# 130808_AriloRX_FINAL_LOGO.net
KiCad netlist of a schematic drawn in EAGLE
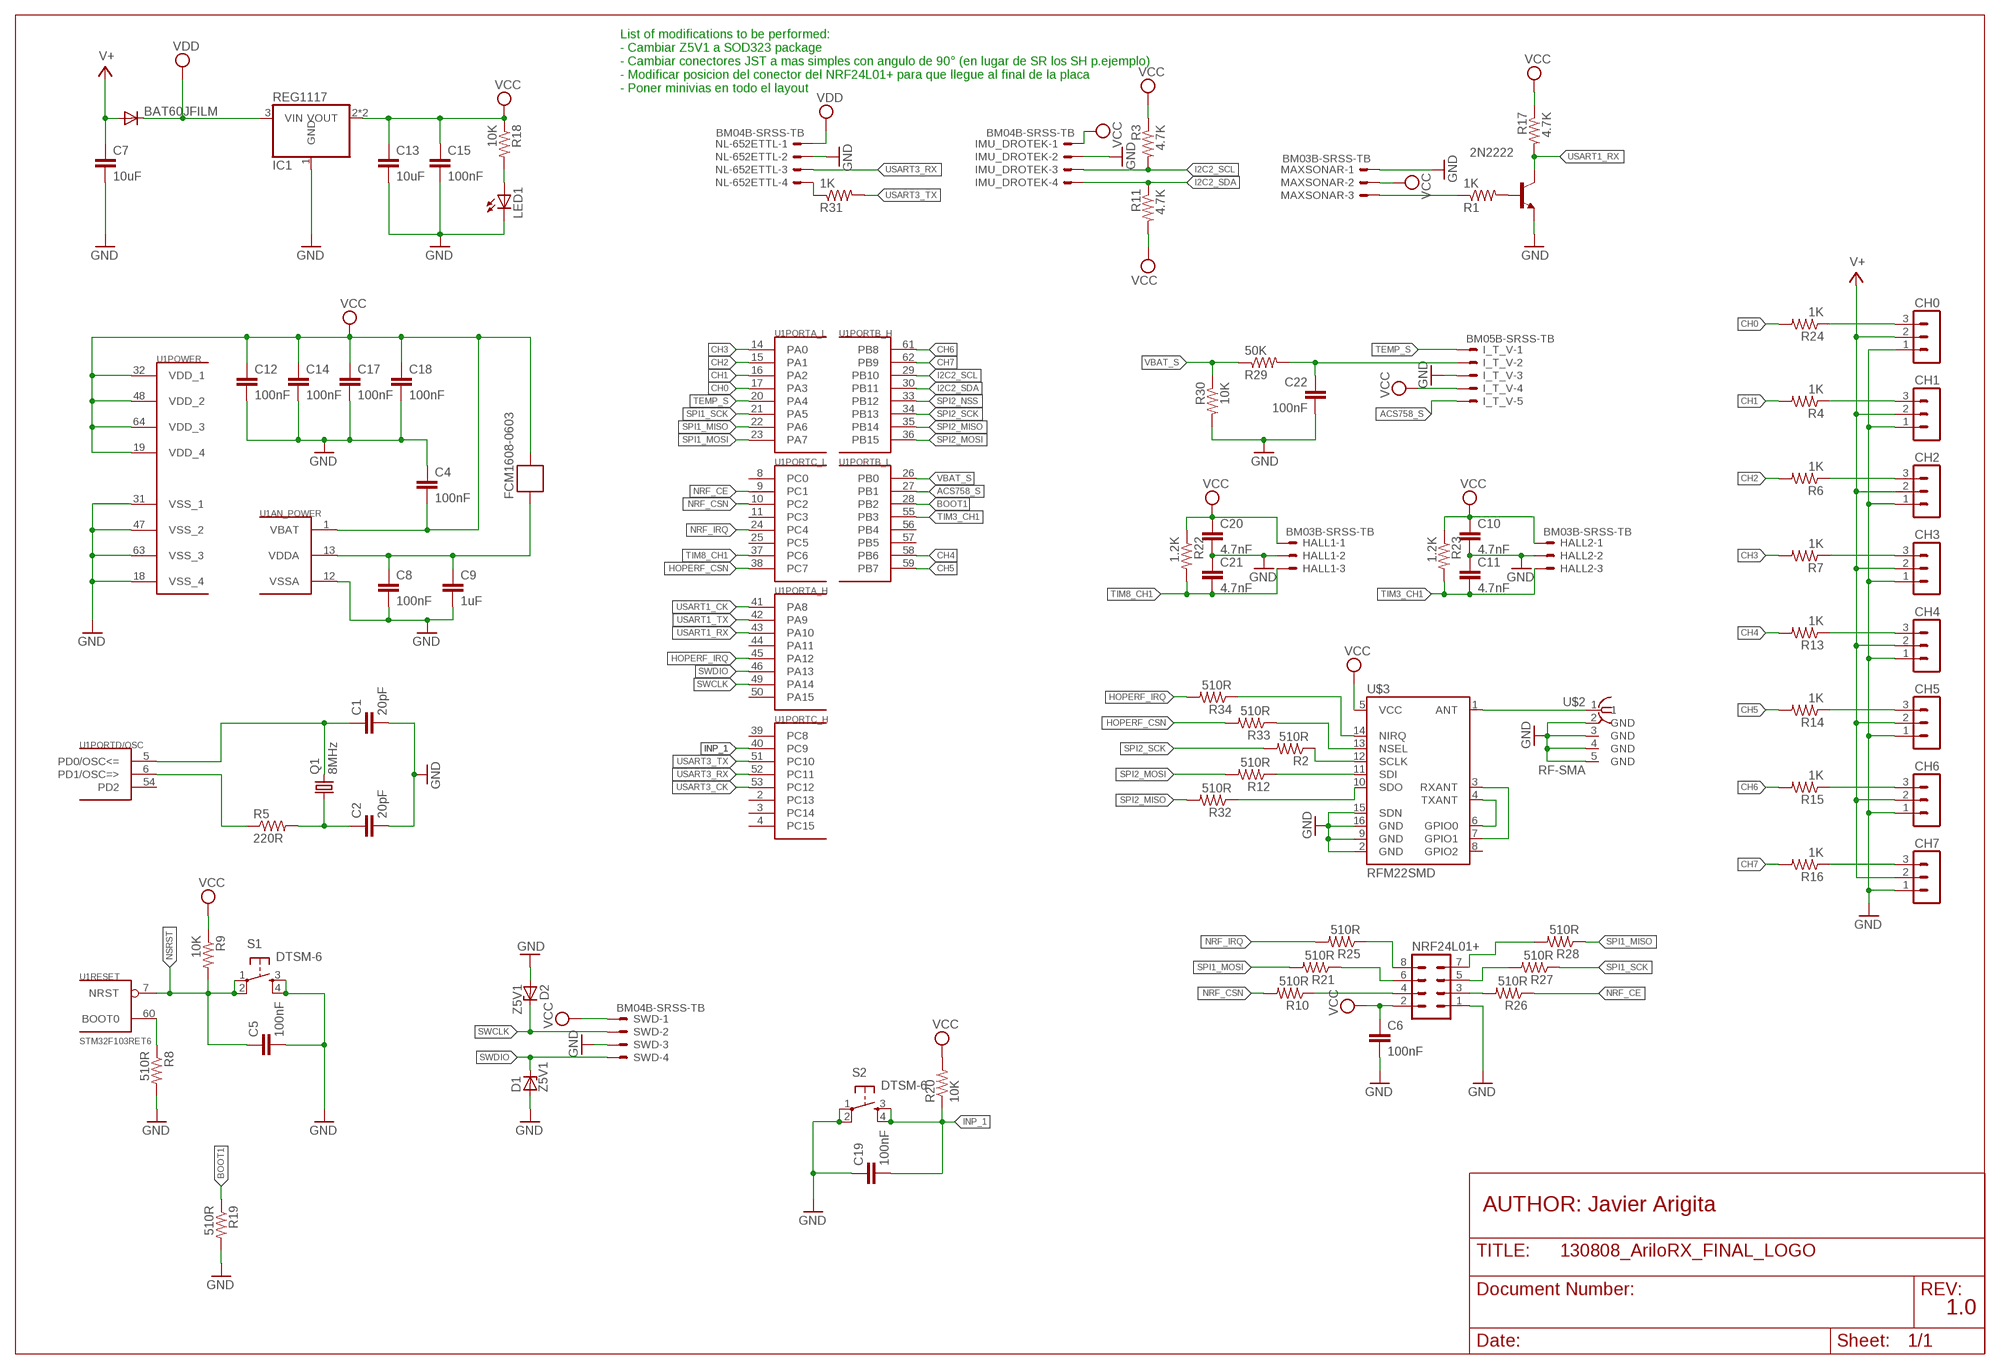
[diagram p0: schematic, sheet 1]

(export (version "E")
  (design (tool "Eeschema 10.0.6"))
  (components
    (comp (ref "2N2222")
      (value "MMBT2222ALT1-NPN-SOT23-BEC")
      (footprint "eagle-import:SOT23-BEC")
      (libsource (lib "eagle-import") (part "-NPN-SOT23-BECMMBT2222ALT1"))
    )
    (comp (ref "BAT60JFILM")
      (value "DIODE-SOD323-R")
      (footprint "eagle-import:SOD323-R")
      (libsource (lib "eagle-import") (part "DIODE-SOD323-R"))
    )
    (comp (ref "C1")
      (value "20pF")
      (footprint "eagle-import:C0805")
      (libsource (lib "eagle-import") (part "C-EUC0805"))
    )
    (comp (ref "C2")
      (value "20pF")
      (footprint "eagle-import:C0805")
      (libsource (lib "eagle-import") (part "C-EUC0805"))
    )
    (comp (ref "C4")
      (value "100nF")
      (footprint "eagle-import:C0805")
      (libsource (lib "eagle-import") (part "C-EUC0805"))
    )
    (comp (ref "C5")
      (value "100nF")
      (footprint "eagle-import:C0805")
      (libsource (lib "eagle-import") (part "C-EUC0805"))
    )
    (comp (ref "C6")
      (value "100nF")
      (footprint "eagle-import:C0805")
      (libsource (lib "eagle-import") (part "C-EUC0805"))
    )
    (comp (ref "C7")
      (value "10uF")
      (footprint "eagle-import:C3216")
      (libsource (lib "eagle-import") (part "resistor_C-EUC3216"))
    )
    (comp (ref "C8")
      (value "100nF")
      (footprint "eagle-import:C0805")
      (libsource (lib "eagle-import") (part "C-EUC0805"))
    )
    (comp (ref "C9")
      (value "1uF")
      (footprint "eagle-import:C3216")
      (libsource (lib "eagle-import") (part "resistor_C-EUC3216"))
    )
    (comp (ref "C10")
      (value "4.7nF")
      (footprint "eagle-import:C0805")
      (libsource (lib "eagle-import") (part "C-EUC0805"))
    )
    (comp (ref "C11")
      (value "4.7nF")
      (footprint "eagle-import:C0805")
      (libsource (lib "eagle-import") (part "C-EUC0805"))
    )
    (comp (ref "C12")
      (value "100nF")
      (footprint "eagle-import:C0805")
      (libsource (lib "eagle-import") (part "C-EUC0805"))
    )
    (comp (ref "C13")
      (value "10uF")
      (footprint "eagle-import:C3216")
      (libsource (lib "eagle-import") (part "resistor_C-EUC3216"))
    )
    (comp (ref "C14")
      (value "100nF")
      (footprint "eagle-import:C0805")
      (libsource (lib "eagle-import") (part "C-EUC0805"))
    )
    (comp (ref "C15")
      (value "100nF")
      (footprint "eagle-import:C0805")
      (libsource (lib "eagle-import") (part "C-EUC0805"))
    )
    (comp (ref "C17")
      (value "100nF")
      (footprint "eagle-import:C0805")
      (libsource (lib "eagle-import") (part "C-EUC0805"))
    )
    (comp (ref "C18")
      (value "100nF")
      (footprint "eagle-import:C0805")
      (libsource (lib "eagle-import") (part "C-EUC0805"))
    )
    (comp (ref "C19")
      (value "100nF")
      (footprint "eagle-import:C0805")
      (libsource (lib "eagle-import") (part "C-EUC0805"))
    )
    (comp (ref "C20")
      (value "4.7nF")
      (footprint "eagle-import:C0805")
      (libsource (lib "eagle-import") (part "C-EUC0805"))
    )
    (comp (ref "C21")
      (value "4.7nF")
      (footprint "eagle-import:C0805")
      (libsource (lib "eagle-import") (part "C-EUC0805"))
    )
    (comp (ref "C22")
      (value "100nF")
      (footprint "eagle-import:C0805")
      (libsource (lib "eagle-import") (part "C-EUC0805"))
    )
    (comp (ref "CH0")
      (value "MA03-1")
      (footprint "eagle-import:MA03-1")
      (libsource (lib "eagle-import") (part "MA03-1"))
    )
    (comp (ref "CH1")
      (value "MA03-1")
      (footprint "eagle-import:MA03-1")
      (libsource (lib "eagle-import") (part "MA03-1"))
    )
    (comp (ref "CH2")
      (value "MA03-1")
      (footprint "eagle-import:MA03-1")
      (libsource (lib "eagle-import") (part "MA03-1"))
    )
    (comp (ref "CH3")
      (value "MA03-1")
      (footprint "eagle-import:MA03-1")
      (libsource (lib "eagle-import") (part "MA03-1"))
    )
    (comp (ref "CH4")
      (value "MA03-1")
      (footprint "eagle-import:MA03-1")
      (libsource (lib "eagle-import") (part "MA03-1"))
    )
    (comp (ref "CH5")
      (value "MA03-1")
      (footprint "eagle-import:MA03-1")
      (libsource (lib "eagle-import") (part "MA03-1"))
    )
    (comp (ref "CH6")
      (value "MA03-1")
      (footprint "eagle-import:MA03-1")
      (libsource (lib "eagle-import") (part "MA03-1"))
    )
    (comp (ref "CH7")
      (value "MA03-1")
      (footprint "eagle-import:MA03-1")
      (libsource (lib "eagle-import") (part "MA03-1"))
    )
    (comp (ref "D1")
      (value "Z5V1")
      (footprint "eagle-import:SOD80C")
      (libsource (lib "eagle-import") (part "ZENER-DIODESOD80C"))
    )
    (comp (ref "D2")
      (value "Z5V1")
      (footprint "eagle-import:SOD80C")
      (libsource (lib "eagle-import") (part "ZENER-DIODESOD80C"))
    )
    (comp (ref "FCM1608-0603")
      (value "FERRITE-BEAD")
      (footprint "eagle-import:R0603")
      (libsource (lib "eagle-import") (part "FERRITE-BEAD"))
    )
    (comp (ref "HALL1")
      (value "BM03B-SRSS-TB")
      (footprint "eagle-import:BM03B-SRSS-TB")
      (libsource (lib "eagle-import") (part "?M03B-SRSS-TBB"))
    )
    (comp (ref "HALL2")
      (value "BM03B-SRSS-TB")
      (footprint "eagle-import:BM03B-SRSS-TB")
      (libsource (lib "eagle-import") (part "?M03B-SRSS-TBB"))
    )
    (comp (ref "IC1")
      (value "REG1117")
      (footprint "eagle-import:SOT223")
      (libsource (lib "eagle-import") (part "REG1117"))
    )
    (comp (ref "IMU_DROTEK")
      (value "BM04B-SRSS-TB")
      (footprint "eagle-import:BM04B-SRSS-TB")
      (libsource (lib "eagle-import") (part "?M04B-SRSS-TBB"))
    )
    (comp (ref "I_T_V")
      (value "BM05B-SRSS-TB")
      (footprint "eagle-import:BM05B-SRSS-TB")
      (libsource (lib "eagle-import") (part "?M05B-SRSS-TBB"))
    )
    (comp (ref "LED1")
      (value "LED0805")
      (footprint "eagle-import:CHIPLED_0805")
      (libsource (lib "eagle-import") (part "LED0805"))
    )
    (comp (ref "MAXSONAR")
      (value "BM03B-SRSS-TB")
      (footprint "eagle-import:BM03B-SRSS-TB")
      (libsource (lib "eagle-import") (part "?M03B-SRSS-TBB"))
    )
    (comp (ref "NL-652ETTL")
      (value "BM04B-SRSS-TB")
      (footprint "eagle-import:BM04B-SRSS-TB")
      (libsource (lib "eagle-import") (part "?M04B-SRSS-TBB"))
    )
    (comp (ref "NRF24L01+")
      (value "MA04-2")
      (footprint "eagle-import:MA04-2")
      (libsource (lib "eagle-import") (part "MA04-2"))
    )
    (comp (ref "Q1")
      (value "8MHz")
      (footprint "eagle-import:SM49")
      (libsource (lib "eagle-import") (part "CRYSTALSM49"))
    )
    (comp (ref "R1")
      (value "1K")
      (footprint "eagle-import:R0805")
      (libsource (lib "eagle-import") (part "RESISTOR0805"))
    )
    (comp (ref "R2")
      (value "510R")
      (footprint "eagle-import:R0805")
      (libsource (lib "eagle-import") (part "RESISTOR0805"))
    )
    (comp (ref "R3")
      (value "4.7K")
      (footprint "eagle-import:R0805")
      (libsource (lib "eagle-import") (part "RESISTOR0805"))
    )
    (comp (ref "R4")
      (value "1K")
      (footprint "eagle-import:R0805")
      (libsource (lib "eagle-import") (part "RESISTOR0805"))
    )
    (comp (ref "R5")
      (value "220R")
      (footprint "eagle-import:R0805")
      (libsource (lib "eagle-import") (part "RESISTOR0805"))
    )
    (comp (ref "R6")
      (value "1K")
      (footprint "eagle-import:R0805")
      (libsource (lib "eagle-import") (part "RESISTOR0805"))
    )
    (comp (ref "R7")
      (value "1K")
      (footprint "eagle-import:R0805")
      (libsource (lib "eagle-import") (part "RESISTOR0805"))
    )
    (comp (ref "R8")
      (value "510R")
      (footprint "eagle-import:R0805")
      (libsource (lib "eagle-import") (part "RESISTOR0805"))
    )
    (comp (ref "R9")
      (value "10K")
      (footprint "eagle-import:R0805")
      (libsource (lib "eagle-import") (part "RESISTOR0805"))
    )
    (comp (ref "R10")
      (value "510R")
      (footprint "eagle-import:R0805")
      (libsource (lib "eagle-import") (part "RESISTOR0805"))
    )
    (comp (ref "R11")
      (value "4.7K")
      (footprint "eagle-import:R0805")
      (libsource (lib "eagle-import") (part "RESISTOR0805"))
    )
    (comp (ref "R12")
      (value "510R")
      (footprint "eagle-import:R0805")
      (libsource (lib "eagle-import") (part "RESISTOR0805"))
    )
    (comp (ref "R13")
      (value "1K")
      (footprint "eagle-import:R0805")
      (libsource (lib "eagle-import") (part "RESISTOR0805"))
    )
    (comp (ref "R14")
      (value "1K")
      (footprint "eagle-import:R0805")
      (libsource (lib "eagle-import") (part "RESISTOR0805"))
    )
    (comp (ref "R15")
      (value "1K")
      (footprint "eagle-import:R0805")
      (libsource (lib "eagle-import") (part "RESISTOR0805"))
    )
    (comp (ref "R16")
      (value "1K")
      (footprint "eagle-import:R0805")
      (libsource (lib "eagle-import") (part "RESISTOR0805"))
    )
    (comp (ref "R17")
      (value "4.7K")
      (footprint "eagle-import:R0805")
      (libsource (lib "eagle-import") (part "RESISTOR0805"))
    )
    (comp (ref "R18")
      (value "10K")
      (footprint "eagle-import:R0805")
      (libsource (lib "eagle-import") (part "RESISTOR0805"))
    )
    (comp (ref "R19")
      (value "510R")
      (footprint "eagle-import:R0805")
      (libsource (lib "eagle-import") (part "RESISTOR0805"))
    )
    (comp (ref "R20")
      (value "10K")
      (footprint "eagle-import:R0805")
      (libsource (lib "eagle-import") (part "RESISTOR0805"))
    )
    (comp (ref "R21")
      (value "510R")
      (footprint "eagle-import:R0805")
      (libsource (lib "eagle-import") (part "RESISTOR0805"))
    )
    (comp (ref "R22")
      (value "1.2K")
      (footprint "eagle-import:R0805")
      (libsource (lib "eagle-import") (part "RESISTOR0805"))
    )
    (comp (ref "R23")
      (value "1.2K")
      (footprint "eagle-import:R0805")
      (libsource (lib "eagle-import") (part "RESISTOR0805"))
    )
    (comp (ref "R24")
      (value "1K")
      (footprint "eagle-import:R0805")
      (libsource (lib "eagle-import") (part "RESISTOR0805"))
    )
    (comp (ref "R25")
      (value "510R")
      (footprint "eagle-import:R0805")
      (libsource (lib "eagle-import") (part "RESISTOR0805"))
    )
    (comp (ref "R26")
      (value "510R")
      (footprint "eagle-import:R0805")
      (libsource (lib "eagle-import") (part "RESISTOR0805"))
    )
    (comp (ref "R27")
      (value "510R")
      (footprint "eagle-import:R0805")
      (libsource (lib "eagle-import") (part "RESISTOR0805"))
    )
    (comp (ref "R28")
      (value "510R")
      (footprint "eagle-import:R0805")
      (libsource (lib "eagle-import") (part "RESISTOR0805"))
    )
    (comp (ref "R29")
      (value "50K")
      (footprint "eagle-import:R0805")
      (libsource (lib "eagle-import") (part "RESISTOR0805"))
    )
    (comp (ref "R30")
      (value "10K")
      (footprint "eagle-import:R0805")
      (libsource (lib "eagle-import") (part "RESISTOR0805"))
    )
    (comp (ref "R31")
      (value "1K")
      (footprint "eagle-import:R0805")
      (libsource (lib "eagle-import") (part "RESISTOR0805"))
    )
    (comp (ref "R32")
      (value "510R")
      (footprint "eagle-import:R0805")
      (libsource (lib "eagle-import") (part "RESISTOR0805"))
    )
    (comp (ref "R33")
      (value "510R")
      (footprint "eagle-import:R0805")
      (libsource (lib "eagle-import") (part "RESISTOR0805"))
    )
    (comp (ref "R34")
      (value "510R")
      (footprint "eagle-import:R0805")
      (libsource (lib "eagle-import") (part "RESISTOR0805"))
    )
    (comp (ref "S1")
      (value "DTSM-6")
      (footprint "eagle-import:DTSM-6")
      (libsource (lib "eagle-import") (part "DTSM-6"))
    )
    (comp (ref "S2")
      (value "DTSM-6")
      (footprint "eagle-import:DTSM-6")
      (libsource (lib "eagle-import") (part "DTSM-6"))
    )
    (comp (ref "SWD")
      (value "BM04B-SRSS-TB")
      (footprint "eagle-import:BM04B-SRSS-TB")
      (libsource (lib "eagle-import") (part "?M04B-SRSS-TBB"))
    )
    (comp (ref "U$2")
      (value "RF-SMA")
      (footprint "eagle-import:BU-SMA-H")
      (libsource (lib "eagle-import") (part "RF-SMA"))
    )
    (comp (ref "U$3")
      (value "RFM22SMD")
      (footprint "eagle-import:RFM22-XXX-S2")
      (libsource (lib "eagle-import") (part "RFM22SMD"))
    )
    (comp (ref "U1")
      (value "STM32F103RET6")
      (footprint "eagle-import:TQFP64")
      (libsource (lib "eagle-import") (part "STM32F10XRXT6"))
    )
  )
  (nets
    (net (code "1") (name "ACS758_S") (class "Default")
      (node (ref "I_T_V") (pin "5") (pinfunction "S_5") (pintype "passive"))
      (node (ref "U1") (pin "27") (pinfunction "PB1_27") (pintype "bidirectional"))
    )
    (net (code "2") (name "BOOT1") (class "Default")
      (node (ref "R19") (pin "1") (pinfunction "1_1") (pintype "passive"))
      (node (ref "U1") (pin "28") (pinfunction "PB2_28") (pintype "bidirectional"))
    )
    (net (code "3") (name "CH0") (class "Default")
      (node (ref "R24") (pin "2") (pinfunction "2_2") (pintype "passive"))
      (node (ref "U1") (pin "17") (pinfunction "PA3_17") (pintype "bidirectional"))
    )
    (net (code "4") (name "CH1") (class "Default")
      (node (ref "R4") (pin "2") (pinfunction "2_2") (pintype "passive"))
      (node (ref "U1") (pin "16") (pinfunction "PA2_16") (pintype "bidirectional"))
    )
    (net (code "5") (name "CH2") (class "Default")
      (node (ref "R6") (pin "2") (pinfunction "2_2") (pintype "passive"))
      (node (ref "U1") (pin "15") (pinfunction "PA1_15") (pintype "bidirectional"))
    )
    (net (code "6") (name "CH3") (class "Default")
      (node (ref "R7") (pin "2") (pinfunction "2_2") (pintype "passive"))
      (node (ref "U1") (pin "14") (pinfunction "PA0_14") (pintype "bidirectional"))
    )
    (net (code "7") (name "CH4") (class "Default")
      (node (ref "R13") (pin "2") (pinfunction "2_2") (pintype "passive"))
      (node (ref "U1") (pin "58") (pinfunction "PB6_58") (pintype "bidirectional"))
    )
    (net (code "8") (name "CH5") (class "Default")
      (node (ref "R14") (pin "2") (pinfunction "2_2") (pintype "passive"))
      (node (ref "U1") (pin "59") (pinfunction "PB7_59") (pintype "bidirectional"))
    )
    (net (code "9") (name "CH6") (class "Default")
      (node (ref "R15") (pin "2") (pinfunction "2_2") (pintype "passive"))
      (node (ref "U1") (pin "61") (pinfunction "PB8_61") (pintype "bidirectional"))
    )
    (net (code "10") (name "CH7") (class "Default")
      (node (ref "R16") (pin "2") (pinfunction "2_2") (pintype "passive"))
      (node (ref "U1") (pin "62") (pinfunction "PB9_62") (pintype "bidirectional"))
    )
    (net (code "11") (name "GND") (class "Default")
      (node (ref "2N2222") (pin "E") (pinfunction "E_E") (pintype "passive"))
      (node (ref "C1") (pin "2") (pinfunction "2_2") (pintype "passive"))
      (node (ref "C10") (pin "2") (pinfunction "2_2") (pintype "passive"))
      (node (ref "C11") (pin "1") (pinfunction "1_1") (pintype "passive"))
      (node (ref "C12") (pin "2") (pinfunction "2_2") (pintype "passive"))
      (node (ref "C13") (pin "2") (pinfunction "2_2") (pintype "passive"))
      (node (ref "C14") (pin "2") (pinfunction "2_2") (pintype "passive"))
      (node (ref "C15") (pin "2") (pinfunction "2_2") (pintype "passive"))
      (node (ref "C17") (pin "2") (pinfunction "2_2") (pintype "passive"))
      (node (ref "C18") (pin "2") (pinfunction "2_2") (pintype "passive"))
      (node (ref "C19") (pin "1") (pinfunction "1_1") (pintype "passive"))
      (node (ref "C2") (pin "2") (pinfunction "2_2") (pintype "passive"))
      (node (ref "C20") (pin "2") (pinfunction "2_2") (pintype "passive"))
      (node (ref "C21") (pin "1") (pinfunction "1_1") (pintype "passive"))
      (node (ref "C22") (pin "2") (pinfunction "2_2") (pintype "passive"))
      (node (ref "C4") (pin "1") (pinfunction "1_1") (pintype "passive"))
      (node (ref "C5") (pin "2") (pinfunction "2_2") (pintype "passive"))
      (node (ref "C6") (pin "2") (pinfunction "2_2") (pintype "passive"))
      (node (ref "C7") (pin "2") (pinfunction "2_2") (pintype "passive"))
      (node (ref "C8") (pin "2") (pinfunction "2_2") (pintype "passive"))
      (node (ref "C9") (pin "2") (pinfunction "2_2") (pintype "passive"))
      (node (ref "CH0") (pin "1") (pinfunction "1_1") (pintype "passive"))
      (node (ref "CH1") (pin "1") (pinfunction "1_1") (pintype "passive"))
      (node (ref "CH2") (pin "1") (pinfunction "1_1") (pintype "passive"))
      (node (ref "CH3") (pin "1") (pinfunction "1_1") (pintype "passive"))
      (node (ref "CH4") (pin "1") (pinfunction "1_1") (pintype "passive"))
      (node (ref "CH5") (pin "1") (pinfunction "1_1") (pintype "passive"))
      (node (ref "CH6") (pin "1") (pinfunction "1_1") (pintype "passive"))
      (node (ref "CH7") (pin "1") (pinfunction "1_1") (pintype "passive"))
      (node (ref "D1") (pin "A") (pinfunction "A_A") (pintype "passive"))
      (node (ref "D2") (pin "A") (pinfunction "A_A") (pintype "passive"))
      (node (ref "HALL1") (pin "2") (pinfunction "S_2") (pintype "passive"))
      (node (ref "HALL2") (pin "2") (pinfunction "S_2") (pintype "passive"))
      (node (ref "IC1") (pin "1") (pinfunction "GND_1") (pintype "power_in"))
      (node (ref "IMU_DROTEK") (pin "2") (pinfunction "S_2") (pintype "passive"))
      (node (ref "I_T_V") (pin "3") (pinfunction "S_3") (pintype "passive"))
      (node (ref "LED1") (pin "C") (pinfunction "C_C") (pintype "passive"))
      (node (ref "MAXSONAR") (pin "1") (pinfunction "S_1") (pintype "passive"))
      (node (ref "NL-652ETTL") (pin "2") (pinfunction "S_2") (pintype "passive"))
      (node (ref "NRF24L01+") (pin "1") (pinfunction "1_1") (pintype "passive"))
      (node (ref "R19") (pin "2") (pinfunction "2_2") (pintype "passive"))
      (node (ref "R30") (pin "2") (pinfunction "2_2") (pintype "passive"))
      (node (ref "R8") (pin "2") (pinfunction "2_2") (pintype "passive"))
      (node (ref "S1") (pin "3") (pinfunction "3_3") (pintype "passive"))
      (node (ref "S1") (pin "4") (pinfunction "4_4") (pintype "passive"))
      (node (ref "S2") (pin "1") (pinfunction "1_1") (pintype "passive"))
      (node (ref "S2") (pin "2") (pinfunction "2_2") (pintype "passive"))
      (node (ref "SWD") (pin "3") (pinfunction "S_3") (pintype "passive"))
      (node (ref "U$2") (pin "2") (pinfunction "GND_2") (pintype "power_in"))
      (node (ref "U$2") (pin "3") (pinfunction "GND_3") (pintype "bidirectional"))
      (node (ref "U$2") (pin "4") (pinfunction "GND_4") (pintype "bidirectional"))
      (node (ref "U$2") (pin "5") (pinfunction "GND_5") (pintype "bidirectional"))
      (node (ref "U$3") (pin "15") (pinfunction "SDN_15") (pintype "input"))
      (node (ref "U$3") (pin "16") (pinfunction "GND_16") (pintype "power_in"))
      (node (ref "U$3") (pin "2") (pinfunction "GND_2") (pintype "power_in"))
      (node (ref "U$3") (pin "9") (pinfunction "GND_9") (pintype "power_in"))
      (node (ref "U1") (pin "12") (pinfunction "VSSA_12") (pintype "power_in"))
      (node (ref "U1") (pin "18") (pinfunction "VSS_4_18") (pintype "power_in"))
      (node (ref "U1") (pin "31") (pinfunction "VSS_1_31") (pintype "power_in"))
      (node (ref "U1") (pin "47") (pinfunction "VSS_2_47") (pintype "power_in"))
      (node (ref "U1") (pin "63") (pinfunction "VSS_3_63") (pintype "power_in"))
    )
    (net (code "12") (name "HOPERF_CSN") (class "Default")
      (node (ref "R33") (pin "2") (pinfunction "2_2") (pintype "passive"))
      (node (ref "U1") (pin "38") (pinfunction "PC7_38") (pintype "bidirectional"))
    )
    (net (code "13") (name "HOPERF_IRQ") (class "Default")
      (node (ref "R34") (pin "2") (pinfunction "2_2") (pintype "passive"))
      (node (ref "U1") (pin "45") (pinfunction "PA12_45") (pintype "bidirectional"))
    )
    (net (code "14") (name "I2C2_SCL") (class "Default")
      (node (ref "IMU_DROTEK") (pin "3") (pinfunction "S_3") (pintype "passive"))
      (node (ref "R3") (pin "2") (pinfunction "2_2") (pintype "passive"))
      (node (ref "U1") (pin "29") (pinfunction "PB10_29") (pintype "bidirectional"))
    )
    (net (code "15") (name "I2C2_SDA") (class "Default")
      (node (ref "IMU_DROTEK") (pin "4") (pinfunction "S_4") (pintype "passive"))
      (node (ref "R11") (pin "1") (pinfunction "1_1") (pintype "passive"))
      (node (ref "U1") (pin "30") (pinfunction "PB11_30") (pintype "bidirectional"))
    )
    (net (code "16") (name "INP_1") (class "Default")
      (node (ref "C19") (pin "2") (pinfunction "2_2") (pintype "passive"))
      (node (ref "R20") (pin "1") (pinfunction "1_1") (pintype "passive"))
      (node (ref "S2") (pin "3") (pinfunction "3_3") (pintype "passive"))
      (node (ref "S2") (pin "4") (pinfunction "4_4") (pintype "passive"))
      (node (ref "U1") (pin "40") (pinfunction "PC9_40") (pintype "bidirectional"))
    )
    (net (code "17") (name "NRF_CE") (class "Default")
      (node (ref "R26") (pin "1") (pinfunction "1_1") (pintype "passive"))
      (node (ref "U1") (pin "9") (pinfunction "PC1_9") (pintype "bidirectional"))
    )
    (net (code "18") (name "NRF_CSN") (class "Default")
      (node (ref "R10") (pin "2") (pinfunction "2_2") (pintype "passive"))
      (node (ref "U1") (pin "10") (pinfunction "PC2_10") (pintype "bidirectional"))
    )
    (net (code "19") (name "NRF_IRQ") (class "Default")
      (node (ref "R25") (pin "2") (pinfunction "2_2") (pintype "passive"))
      (node (ref "U1") (pin "24") (pinfunction "PC4_24") (pintype "bidirectional"))
    )
    (net (code "20") (name "NSRST") (class "Default")
      (node (ref "C5") (pin "1") (pinfunction "1_1") (pintype "passive"))
      (node (ref "R9") (pin "2") (pinfunction "2_2") (pintype "passive"))
      (node (ref "S1") (pin "1") (pinfunction "1_1") (pintype "passive"))
      (node (ref "S1") (pin "2") (pinfunction "2_2") (pintype "passive"))
      (node (ref "U1") (pin "7") (pinfunction "NRST_7") (pintype "input"))
    )
    (net (code "21") (name "Net-(2N2222-PadB)") (class "Default")
      (node (ref "2N2222") (pin "B") (pinfunction "B_B") (pintype "passive"))
      (node (ref "R1") (pin "2") (pinfunction "2_2") (pintype "passive"))
    )
    (net (code "22") (name "Net-(C2-Pad1)") (class "Default")
      (node (ref "C2") (pin "1") (pinfunction "1_1") (pintype "passive"))
      (node (ref "Q1") (pin "1") (pinfunction "1_1") (pintype "passive"))
      (node (ref "R5") (pin "2") (pinfunction "2_2") (pintype "passive"))
    )
    (net (code "23") (name "Net-(CH0-Pad3)") (class "Default")
      (node (ref "CH0") (pin "3") (pinfunction "3_3") (pintype "passive"))
      (node (ref "R24") (pin "1") (pinfunction "1_1") (pintype "passive"))
    )
    (net (code "24") (name "Net-(CH1-Pad3)") (class "Default")
      (node (ref "CH1") (pin "3") (pinfunction "3_3") (pintype "passive"))
      (node (ref "R4") (pin "1") (pinfunction "1_1") (pintype "passive"))
    )
    (net (code "25") (name "Net-(CH2-Pad3)") (class "Default")
      (node (ref "CH2") (pin "3") (pinfunction "3_3") (pintype "passive"))
      (node (ref "R6") (pin "1") (pinfunction "1_1") (pintype "passive"))
    )
    (net (code "26") (name "Net-(CH3-Pad3)") (class "Default")
      (node (ref "CH3") (pin "3") (pinfunction "3_3") (pintype "passive"))
      (node (ref "R7") (pin "1") (pinfunction "1_1") (pintype "passive"))
    )
    (net (code "27") (name "Net-(CH4-Pad3)") (class "Default")
      (node (ref "CH4") (pin "3") (pinfunction "3_3") (pintype "passive"))
      (node (ref "R13") (pin "1") (pinfunction "1_1") (pintype "passive"))
    )
    (net (code "28") (name "Net-(CH5-Pad3)") (class "Default")
      (node (ref "CH5") (pin "3") (pinfunction "3_3") (pintype "passive"))
      (node (ref "R14") (pin "1") (pinfunction "1_1") (pintype "passive"))
    )
    (net (code "29") (name "Net-(CH6-Pad3)") (class "Default")
      (node (ref "CH6") (pin "3") (pinfunction "3_3") (pintype "passive"))
      (node (ref "R15") (pin "1") (pinfunction "1_1") (pintype "passive"))
    )
    (net (code "30") (name "Net-(CH7-Pad3)") (class "Default")
      (node (ref "CH7") (pin "3") (pinfunction "3_3") (pintype "passive"))
      (node (ref "R16") (pin "1") (pinfunction "1_1") (pintype "passive"))
    )
    (net (code "31") (name "Net-(FCM1608-0603-P$2)") (class "Default")
      (node (ref "C8") (pin "1") (pinfunction "1_1") (pintype "passive"))
      (node (ref "C9") (pin "1") (pinfunction "1_1") (pintype "passive"))
      (node (ref "FCM1608-0603") (pin "2") (pinfunction "P$2_2") (pintype "bidirectional"))
      (node (ref "U1") (pin "13") (pinfunction "VDDA_13") (pintype "power_in"))
    )
    (net (code "32") (name "Net-(I_T_VB-S)") (class "Default")
      (node (ref "C22") (pin "1") (pinfunction "1_1") (pintype "passive"))
      (node (ref "I_T_V") (pin "2") (pinfunction "S_2") (pintype "passive"))
      (node (ref "R29") (pin "2") (pinfunction "2_2") (pintype "passive"))
    )
    (net (code "33") (name "Net-(LED1-PadA)") (class "Default")
      (node (ref "LED1") (pin "A") (pinfunction "A_A") (pintype "passive"))
      (node (ref "R18") (pin "2") (pinfunction "2_2") (pintype "passive"))
    )
    (net (code "34") (name "Net-(MAXSONARC-S)") (class "Default")
      (node (ref "MAXSONAR") (pin "3") (pinfunction "S_3") (pintype "passive"))
      (node (ref "R1") (pin "1") (pinfunction "1_1") (pintype "passive"))
    )
    (net (code "35") (name "Net-(NL-652ETTLD-S)") (class "Default")
      (node (ref "NL-652ETTL") (pin "4") (pinfunction "S_4") (pintype "passive"))
      (node (ref "R31") (pin "1") (pinfunction "1_1") (pintype "passive"))
    )
    (net (code "36") (name "Net-(NRF24L01+-Pad3)") (class "Default")
      (node (ref "NRF24L01+") (pin "3") (pinfunction "3_3") (pintype "passive"))
      (node (ref "R26") (pin "2") (pinfunction "2_2") (pintype "passive"))
    )
    (net (code "37") (name "Net-(NRF24L01+-Pad4)") (class "Default")
      (node (ref "NRF24L01+") (pin "4") (pinfunction "4_4") (pintype "passive"))
      (node (ref "R10") (pin "1") (pinfunction "1_1") (pintype "passive"))
    )
    (net (code "38") (name "Net-(NRF24L01+-Pad5)") (class "Default")
      (node (ref "NRF24L01+") (pin "5") (pinfunction "5_5") (pintype "passive"))
      (node (ref "R27") (pin "2") (pinfunction "2_2") (pintype "passive"))
    )
    (net (code "39") (name "Net-(NRF24L01+-Pad6)") (class "Default")
      (node (ref "NRF24L01+") (pin "6") (pinfunction "6_6") (pintype "passive"))
      (node (ref "R21") (pin "1") (pinfunction "1_1") (pintype "passive"))
    )
    (net (code "40") (name "Net-(NRF24L01+-Pad7)") (class "Default")
      (node (ref "NRF24L01+") (pin "7") (pinfunction "7_7") (pintype "passive"))
      (node (ref "R28") (pin "2") (pinfunction "2_2") (pintype "passive"))
    )
    (net (code "41") (name "Net-(NRF24L01+-Pad8)") (class "Default")
      (node (ref "NRF24L01+") (pin "8") (pinfunction "8_8") (pintype "passive"))
      (node (ref "R25") (pin "1") (pinfunction "1_1") (pintype "passive"))
    )
    (net (code "42") (name "Net-(U$3-ANT)") (class "Default")
      (node (ref "U$2") (pin "1") (pinfunction "1_1") (pintype "passive"))
      (node (ref "U$3") (pin "1") (pinfunction "ANT_1") (pintype "bidirectional"))
    )
    (net (code "43") (name "Net-(U$3-GPIO0)") (class "Default")
      (node (ref "U$3") (pin "4") (pinfunction "TXANT_4") (pintype "input"))
      (node (ref "U$3") (pin "6") (pinfunction "GPIO0_6") (pintype "bidirectional"))
    )
    (net (code "44") (name "Net-(U$3-GPIO1)") (class "Default")
      (node (ref "U$3") (pin "3") (pinfunction "RXANT_3") (pintype "input"))
      (node (ref "U$3") (pin "7") (pinfunction "GPIO1_7") (pintype "bidirectional"))
    )
    (net (code "45") (name "Net-(U$3-NIRQ)") (class "Default")
      (node (ref "R34") (pin "1") (pinfunction "1_1") (pintype "passive"))
      (node (ref "U$3") (pin "14") (pinfunction "NIRQ_14") (pintype "output"))
    )
    (net (code "46") (name "Net-(U$3-NSEL)") (class "Default")
      (node (ref "R33") (pin "1") (pinfunction "1_1") (pintype "passive"))
      (node (ref "U$3") (pin "13") (pinfunction "NSEL_13") (pintype "input"))
    )
    (net (code "47") (name "Net-(U$3-SCLK)") (class "Default")
      (node (ref "R2") (pin "1") (pinfunction "1_1") (pintype "passive"))
      (node (ref "U$3") (pin "12") (pinfunction "SCLK_12") (pintype "input"))
    )
    (net (code "48") (name "Net-(U$3-SDI)") (class "Default")
      (node (ref "R12") (pin "1") (pinfunction "1_1") (pintype "passive"))
      (node (ref "U$3") (pin "11") (pinfunction "SDI_11") (pintype "input"))
    )
    (net (code "49") (name "Net-(U$3-SDO)") (class "Default")
      (node (ref "R32") (pin "1") (pinfunction "1_1") (pintype "passive"))
      (node (ref "U$3") (pin "10") (pinfunction "SDO_10") (pintype "output"))
    )
    (net (code "50") (name "Net-(U1H-PD0{slash}OSC<=)") (class "Default")
      (node (ref "C1") (pin "1") (pinfunction "1_1") (pintype "passive"))
      (node (ref "Q1") (pin "2") (pinfunction "2_2") (pintype "passive"))
      (node (ref "U1") (pin "5") (pinfunction "PD0/OSC<=_5") (pintype "bidirectional"))
    )
    (net (code "51") (name "Net-(U1H-PD1{slash}OSC=>)") (class "Default")
      (node (ref "R5") (pin "1") (pinfunction "1_1") (pintype "passive"))
      (node (ref "U1") (pin "6") (pinfunction "PD1/OSC=>_6") (pintype "bidirectional"))
    )
    (net (code "52") (name "Net-(U1J-BOOT0)") (class "Default")
      (node (ref "R8") (pin "1") (pinfunction "1_1") (pintype "passive"))
      (node (ref "U1") (pin "60") (pinfunction "BOOT0_60") (pintype "input"))
    )
    (net (code "53") (name "SPI1_MISO") (class "Default")
      (node (ref "R28") (pin "1") (pinfunction "1_1") (pintype "passive"))
      (node (ref "U1") (pin "22") (pinfunction "PA6_22") (pintype "bidirectional"))
    )
    (net (code "54") (name "SPI1_MOSI") (class "Default")
      (node (ref "R21") (pin "2") (pinfunction "2_2") (pintype "passive"))
      (node (ref "U1") (pin "23") (pinfunction "PA7_23") (pintype "bidirectional"))
    )
    (net (code "55") (name "SPI1_SCK") (class "Default")
      (node (ref "R27") (pin "1") (pinfunction "1_1") (pintype "passive"))
      (node (ref "U1") (pin "21") (pinfunction "PA5_21") (pintype "bidirectional"))
    )
    (net (code "56") (name "SPI2_MISO") (class "Default")
      (node (ref "R32") (pin "2") (pinfunction "2_2") (pintype "passive"))
      (node (ref "U1") (pin "35") (pinfunction "PB14_35") (pintype "bidirectional"))
    )
    (net (code "57") (name "SPI2_MOSI") (class "Default")
      (node (ref "R12") (pin "2") (pinfunction "2_2") (pintype "passive"))
      (node (ref "U1") (pin "36") (pinfunction "PB15_36") (pintype "bidirectional"))
    )
    (net (code "58") (name "SPI2_NSS") (class "Default")
      (node (ref "U1") (pin "33") (pinfunction "PB12_33") (pintype "bidirectional"))
    )
    (net (code "59") (name "SPI2_SCK") (class "Default")
      (node (ref "R2") (pin "2") (pinfunction "2_2") (pintype "passive"))
      (node (ref "U1") (pin "34") (pinfunction "PB13_34") (pintype "bidirectional"))
    )
    (net (code "60") (name "SWCLK") (class "Default")
      (node (ref "D2") (pin "C") (pinfunction "C_C") (pintype "passive"))
      (node (ref "SWD") (pin "2") (pinfunction "S_2") (pintype "passive"))
      (node (ref "U1") (pin "49") (pinfunction "PA14_49") (pintype "bidirectional"))
    )
    (net (code "61") (name "SWDIO") (class "Default")
      (node (ref "D1") (pin "C") (pinfunction "C_C") (pintype "passive"))
      (node (ref "SWD") (pin "4") (pinfunction "S_4") (pintype "passive"))
      (node (ref "U1") (pin "46") (pinfunction "PA13_46") (pintype "bidirectional"))
    )
    (net (code "62") (name "TEMP_S") (class "Default")
      (node (ref "I_T_V") (pin "1") (pinfunction "S_1") (pintype "passive"))
      (node (ref "U1") (pin "20") (pinfunction "PA4_20") (pintype "bidirectional"))
    )
    (net (code "63") (name "TIM3_CH1") (class "Default")
      (node (ref "C11") (pin "2") (pinfunction "2_2") (pintype "passive"))
      (node (ref "HALL2") (pin "3") (pinfunction "S_3") (pintype "passive"))
      (node (ref "R23") (pin "2") (pinfunction "2_2") (pintype "passive"))
      (node (ref "U1") (pin "55") (pinfunction "PB3_55") (pintype "bidirectional"))
    )
    (net (code "64") (name "TIM8_CH1") (class "Default")
      (node (ref "C21") (pin "2") (pinfunction "2_2") (pintype "passive"))
      (node (ref "HALL1") (pin "3") (pinfunction "S_3") (pintype "passive"))
      (node (ref "R22") (pin "2") (pinfunction "2_2") (pintype "passive"))
      (node (ref "U1") (pin "37") (pinfunction "PC6_37") (pintype "bidirectional"))
    )
    (net (code "65") (name "USART1_CK") (class "Default")
      (node (ref "U1") (pin "41") (pinfunction "PA8_41") (pintype "bidirectional"))
    )
    (net (code "66") (name "USART1_RX") (class "Default")
      (node (ref "2N2222") (pin "C") (pinfunction "C_C") (pintype "passive"))
      (node (ref "R17") (pin "2") (pinfunction "2_2") (pintype "passive"))
      (node (ref "U1") (pin "43") (pinfunction "PA10_43") (pintype "bidirectional"))
    )
    (net (code "67") (name "USART1_TX") (class "Default")
      (node (ref "U1") (pin "42") (pinfunction "PA9_42") (pintype "bidirectional"))
    )
    (net (code "68") (name "USART3_CK") (class "Default")
      (node (ref "U1") (pin "53") (pinfunction "PC12_53") (pintype "bidirectional"))
    )
    (net (code "69") (name "USART3_RX") (class "Default")
      (node (ref "NL-652ETTL") (pin "3") (pinfunction "S_3") (pintype "passive"))
      (node (ref "U1") (pin "52") (pinfunction "PC11_52") (pintype "bidirectional"))
    )
    (net (code "70") (name "USART3_TX") (class "Default")
      (node (ref "R31") (pin "2") (pinfunction "2_2") (pintype "passive"))
      (node (ref "U1") (pin "51") (pinfunction "PC10_51") (pintype "bidirectional"))
    )
    (net (code "71") (name "V+") (class "Default")
      (node (ref "BAT60JFILM") (pin "A") (pinfunction "A_A") (pintype "passive"))
      (node (ref "C7") (pin "1") (pinfunction "1_1") (pintype "passive"))
      (node (ref "CH0") (pin "2") (pinfunction "2_2") (pintype "passive"))
      (node (ref "CH1") (pin "2") (pinfunction "2_2") (pintype "passive"))
      (node (ref "CH2") (pin "2") (pinfunction "2_2") (pintype "passive"))
      (node (ref "CH3") (pin "2") (pinfunction "2_2") (pintype "passive"))
      (node (ref "CH4") (pin "2") (pinfunction "2_2") (pintype "passive"))
      (node (ref "CH5") (pin "2") (pinfunction "2_2") (pintype "passive"))
      (node (ref "CH6") (pin "2") (pinfunction "2_2") (pintype "passive"))
      (node (ref "CH7") (pin "2") (pinfunction "2_2") (pintype "passive"))
    )
    (net (code "72") (name "VBAT_S") (class "Default")
      (node (ref "R29") (pin "1") (pinfunction "1_1") (pintype "passive"))
      (node (ref "R30") (pin "1") (pinfunction "1_1") (pintype "passive"))
      (node (ref "U1") (pin "26") (pinfunction "PB0_26") (pintype "bidirectional"))
    )
    (net (code "73") (name "VCC") (class "Default")
      (node (ref "C10") (pin "1") (pinfunction "1_1") (pintype "passive"))
      (node (ref "C12") (pin "1") (pinfunction "1_1") (pintype "passive"))
      (node (ref "C13") (pin "1") (pinfunction "1_1") (pintype "passive"))
      (node (ref "C14") (pin "1") (pinfunction "1_1") (pintype "passive"))
      (node (ref "C15") (pin "1") (pinfunction "1_1") (pintype "passive"))
      (node (ref "C17") (pin "1") (pinfunction "1_1") (pintype "passive"))
      (node (ref "C18") (pin "1") (pinfunction "1_1") (pintype "passive"))
      (node (ref "C20") (pin "1") (pinfunction "1_1") (pintype "passive"))
      (node (ref "C4") (pin "2") (pinfunction "2_2") (pintype "passive"))
      (node (ref "C6") (pin "1") (pinfunction "1_1") (pintype "passive"))
      (node (ref "FCM1608-0603") (pin "1") (pinfunction "P$1_1") (pintype "bidirectional"))
      (node (ref "HALL1") (pin "1") (pinfunction "S_1") (pintype "passive"))
      (node (ref "HALL2") (pin "1") (pinfunction "S_1") (pintype "passive"))
      (node (ref "IC1") (pin "2") (pinfunction "VOUT_2") (pintype "power_in"))
      (node (ref "IC1") (pin "4") (pinfunction "VOUT_4") (pintype "power_in"))
      (node (ref "IMU_DROTEK") (pin "1") (pinfunction "S_1") (pintype "passive"))
      (node (ref "I_T_V") (pin "4") (pinfunction "S_4") (pintype "passive"))
      (node (ref "MAXSONAR") (pin "2") (pinfunction "S_2") (pintype "passive"))
      (node (ref "NRF24L01+") (pin "2") (pinfunction "2_2") (pintype "passive"))
      (node (ref "R11") (pin "2") (pinfunction "2_2") (pintype "passive"))
      (node (ref "R17") (pin "1") (pinfunction "1_1") (pintype "passive"))
      (node (ref "R18") (pin "1") (pinfunction "1_1") (pintype "passive"))
      (node (ref "R20") (pin "2") (pinfunction "2_2") (pintype "passive"))
      (node (ref "R22") (pin "1") (pinfunction "1_1") (pintype "passive"))
      (node (ref "R23") (pin "1") (pinfunction "1_1") (pintype "passive"))
      (node (ref "R3") (pin "1") (pinfunction "1_1") (pintype "passive"))
      (node (ref "R9") (pin "1") (pinfunction "1_1") (pintype "passive"))
      (node (ref "SWD") (pin "1") (pinfunction "S_1") (pintype "passive"))
      (node (ref "U$3") (pin "5") (pinfunction "VCC_5") (pintype "bidirectional"))
      (node (ref "U1") (pin "1") (pinfunction "VBAT_1") (pintype "power_in"))
      (node (ref "U1") (pin "19") (pinfunction "VDD_4_19") (pintype "power_in"))
      (node (ref "U1") (pin "32") (pinfunction "VDD_1_32") (pintype "power_in"))
      (node (ref "U1") (pin "48") (pinfunction "VDD_2_48") (pintype "power_in"))
      (node (ref "U1") (pin "64") (pinfunction "VDD_3_64") (pintype "power_in"))
    )
    (net (code "74") (name "VDD") (class "Default")
      (node (ref "BAT60JFILM") (pin "C") (pinfunction "C_C") (pintype "passive"))
      (node (ref "IC1") (pin "3") (pinfunction "VIN_3") (pintype "input"))
      (node (ref "NL-652ETTL") (pin "1") (pinfunction "S_1") (pintype "passive"))
    )
    (net (code "75") (name "unconnected-(U$3-GPIO2-Pad8)") (class "Default")
      (node (ref "U$3") (pin "8") (pinfunction "GPIO2_8") (pintype "bidirectional"))
    )
    (net (code "76") (name "unconnected-(U1B-PA11-Pad44)") (class "Default")
      (node (ref "U1") (pin "44") (pinfunction "PA11_44") (pintype "bidirectional"))
    )
    (net (code "77") (name "unconnected-(U1B-PA15-Pad50)") (class "Default")
      (node (ref "U1") (pin "50") (pinfunction "PA15_50") (pintype "bidirectional"))
    )
    (net (code "78") (name "unconnected-(U1E-PB4-Pad56)") (class "Default")
      (node (ref "U1") (pin "56") (pinfunction "PB4_56") (pintype "bidirectional"))
    )
    (net (code "79") (name "unconnected-(U1E-PB5-Pad57)") (class "Default")
      (node (ref "U1") (pin "57") (pinfunction "PB5_57") (pintype "bidirectional"))
    )
    (net (code "80") (name "unconnected-(U1F-PC8-Pad39)") (class "Default")
      (node (ref "U1") (pin "39") (pinfunction "PC8_39") (pintype "bidirectional"))
    )
    (net (code "81") (name "unconnected-(U1F-PC13-Pad2)") (class "Default")
      (node (ref "U1") (pin "2") (pinfunction "PC13_2") (pintype "bidirectional"))
    )
    (net (code "82") (name "unconnected-(U1F-PC14-Pad3)") (class "Default")
      (node (ref "U1") (pin "3") (pinfunction "PC14_3") (pintype "bidirectional"))
    )
    (net (code "83") (name "unconnected-(U1F-PC15-Pad4)") (class "Default")
      (node (ref "U1") (pin "4") (pinfunction "PC15_4") (pintype "bidirectional"))
    )
    (net (code "84") (name "unconnected-(U1G-PC0-Pad8)") (class "Default")
      (node (ref "U1") (pin "8") (pinfunction "PC0_8") (pintype "bidirectional"))
    )
    (net (code "85") (name "unconnected-(U1G-PC3-Pad11)") (class "Default")
      (node (ref "U1") (pin "11") (pinfunction "PC3_11") (pintype "bidirectional"))
    )
    (net (code "86") (name "unconnected-(U1G-PC5-Pad25)") (class "Default")
      (node (ref "U1") (pin "25") (pinfunction "PC5_25") (pintype "bidirectional"))
    )
    (net (code "87") (name "unconnected-(U1H-PD2-Pad54)") (class "Default")
      (node (ref "U1") (pin "54") (pinfunction "PD2_54") (pintype "bidirectional"))
    )
  )
)
